# rev_d.net
KiCad netlist of a schematic drawn in EAGLE
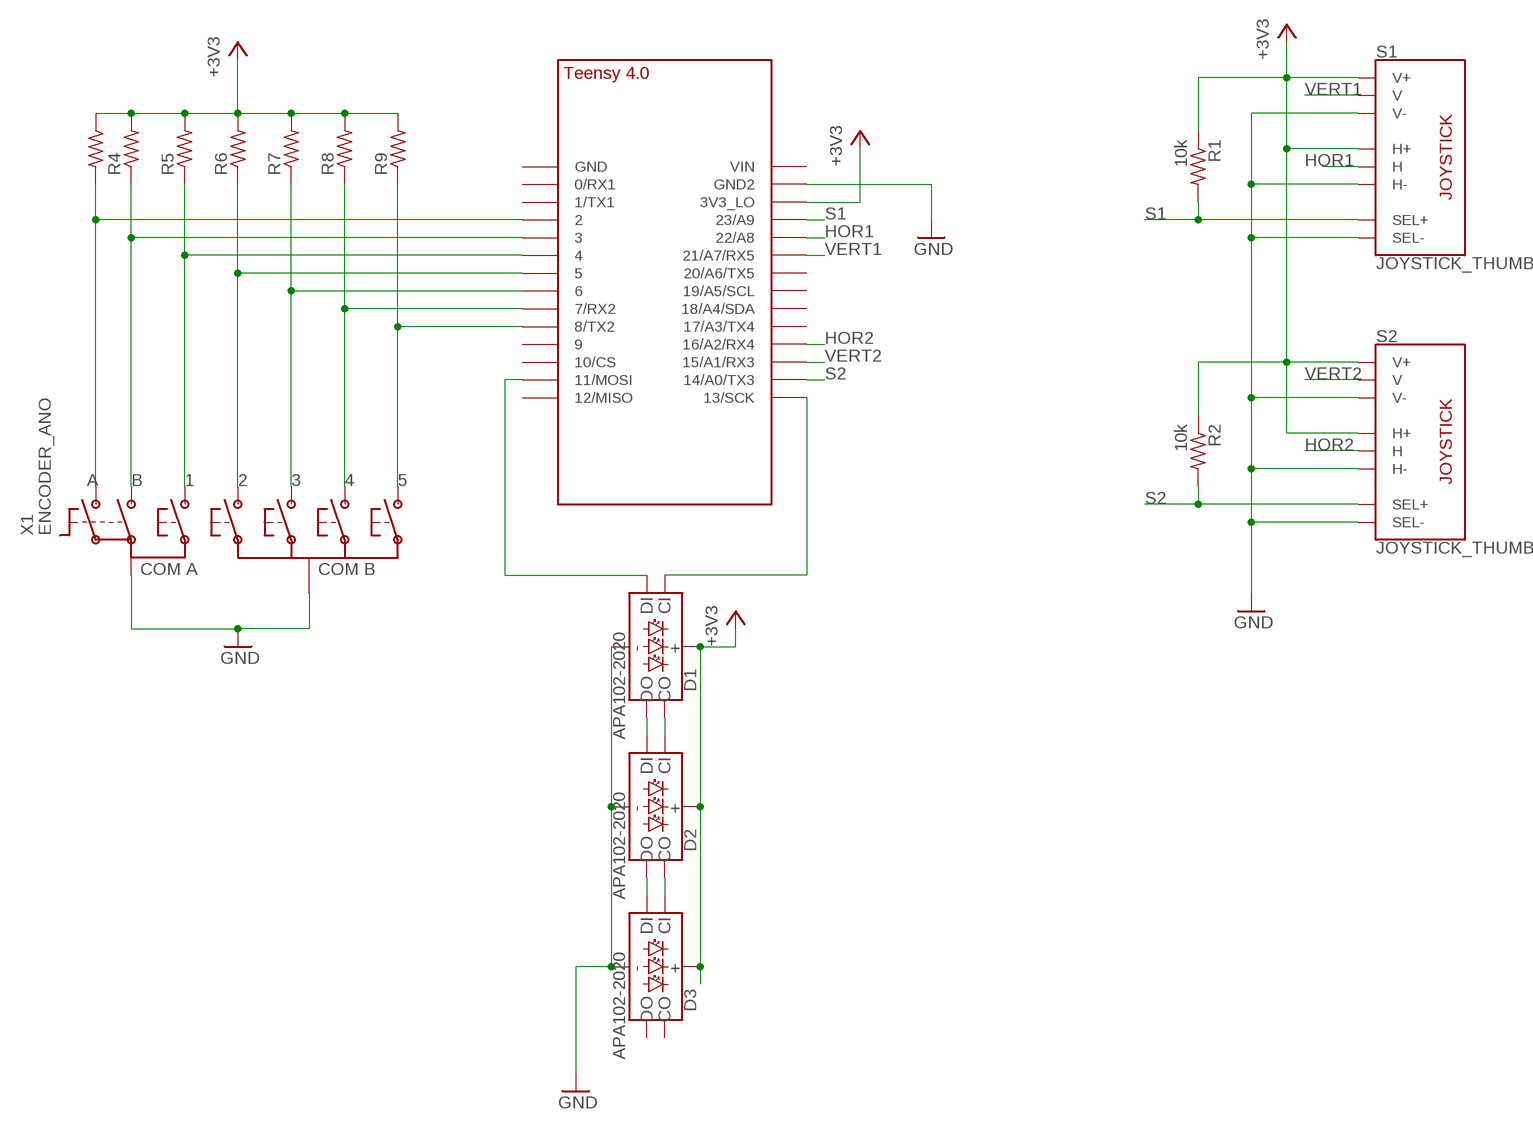
[diagram p0: schematic, sheet 1]

(export (version "E")
  (design (tool "Eeschema 10.0.6"))
  (components
    (comp (ref "D1")
      (value "APA102-2020")
      (footprint "eagle-import:APA102-2020")
      (libsource (lib "eagle-import") (part "APA102-2020"))
    )
    (comp (ref "D2")
      (value "APA102-2020")
      (footprint "eagle-import:APA102-2020")
      (libsource (lib "eagle-import") (part "APA102-2020"))
    )
    (comp (ref "D3")
      (value "APA102-2020")
      (footprint "eagle-import:APA102-2020")
      (libsource (lib "eagle-import") (part "APA102-2020"))
    )
    (comp (ref "MCU")
      (value "TEENSY_4.0-NOBOTTOM")
      (footprint "eagle-import:TEENSY_4.0-NOBOTTOM")
      (libsource (lib "eagle-import") (part "TEENSY_4.0-NOBOTTOM"))
    )
    (comp (ref "R1")
      (value "10k")
      (footprint "eagle-import:R0603")
      (libsource (lib "eagle-import") (part "R-US_R0603"))
    )
    (comp (ref "R2")
      (value "10k")
      (footprint "eagle-import:R0603")
      (libsource (lib "eagle-import") (part "R-US_R0603"))
    )
    (comp (ref "R3")
      (value "10k")
      (footprint "eagle-import:R0603")
      (libsource (lib "eagle-import") (part "R-US_R0603"))
    )
    (comp (ref "R4")
      (value "R-US_R0603")
      (footprint "eagle-import:R0603")
      (libsource (lib "eagle-import") (part "R-US_R0603"))
    )
    (comp (ref "R5")
      (value "R-US_R0603")
      (footprint "eagle-import:R0603")
      (libsource (lib "eagle-import") (part "R-US_R0603"))
    )
    (comp (ref "R6")
      (value "R-US_R0603")
      (footprint "eagle-import:R0603")
      (libsource (lib "eagle-import") (part "R-US_R0603"))
    )
    (comp (ref "R7")
      (value "R-US_R0603")
      (footprint "eagle-import:R0603")
      (libsource (lib "eagle-import") (part "R-US_R0603"))
    )
    (comp (ref "R8")
      (value "R-US_R0603")
      (footprint "eagle-import:R0603")
      (libsource (lib "eagle-import") (part "R-US_R0603"))
    )
    (comp (ref "R9")
      (value "R-US_R0603")
      (footprint "eagle-import:R0603")
      (libsource (lib "eagle-import") (part "R-US_R0603"))
    )
    (comp (ref "S1")
      (value "JOYSTICK_THUMB")
      (footprint "eagle-import:JOYSTICK")
      (libsource (lib "eagle-import") (part "JOYSTICK_THUMB"))
    )
    (comp (ref "S2")
      (value "JOYSTICK_THUMB")
      (footprint "eagle-import:JOYSTICK")
      (libsource (lib "eagle-import") (part "JOYSTICK_THUMB"))
    )
    (comp (ref "X1")
      (value "ENCODER_ANO")
      (footprint "eagle-import:ENCODER_ANO")
      (libsource (lib "eagle-import") (part "ENCODER_ANO"))
    )
  )
  (nets
    (net (code "1") (name "+3V3") (class "Default")
      (node (ref "D1") (pin "VDD") (pinfunction "VCC_VDD") (pintype "bidirectional"))
      (node (ref "D2") (pin "VDD") (pinfunction "VCC_VDD") (pintype "bidirectional"))
      (node (ref "D3") (pin "VDD") (pinfunction "VCC_VDD") (pintype "bidirectional"))
      (node (ref "MCU") (pin "3V3_LO") (pinfunction "3V3_LO_3V3_LO") (pintype "bidirectional"))
      (node (ref "R1") (pin "1") (pinfunction "1_1") (pintype "passive"))
      (node (ref "R2") (pin "1") (pinfunction "1_1") (pintype "passive"))
      (node (ref "R3") (pin "1") (pinfunction "1_1") (pintype "passive"))
      (node (ref "R4") (pin "2") (pinfunction "2_2") (pintype "passive"))
      (node (ref "R5") (pin "2") (pinfunction "2_2") (pintype "passive"))
      (node (ref "R6") (pin "2") (pinfunction "2_2") (pintype "passive"))
      (node (ref "R7") (pin "2") (pinfunction "2_2") (pintype "passive"))
      (node (ref "R8") (pin "2") (pinfunction "2_2") (pintype "passive"))
      (node (ref "R9") (pin "2") (pinfunction "2_2") (pintype "passive"))
      (node (ref "S1") (pin "H1") (pinfunction "H+_H1") (pintype "bidirectional"))
      (node (ref "S1") (pin "V1") (pinfunction "V+_V1") (pintype "bidirectional"))
      (node (ref "S2") (pin "H1") (pinfunction "H+_H1") (pintype "bidirectional"))
      (node (ref "S2") (pin "V1") (pinfunction "V+_V1") (pintype "bidirectional"))
    )
    (net (code "2") (name "/HOR1") (class "Default")
      (node (ref "MCU") (pin "22/A8") (pinfunction "22/A8_22/A8") (pintype "bidirectional"))
      (node (ref "S1") (pin "H2") (pinfunction "H_H2") (pintype "bidirectional"))
    )
    (net (code "3") (name "/HOR2") (class "Default")
      (node (ref "MCU") (pin "16/A2") (pinfunction "16/A2/RX4_16/A2") (pintype "bidirectional"))
      (node (ref "S2") (pin "H2") (pinfunction "H_H2") (pintype "bidirectional"))
    )
    (net (code "4") (name "/S1") (class "Default")
      (node (ref "MCU") (pin "23/A9") (pinfunction "23/A9_23/A9") (pintype "bidirectional"))
      (node (ref "R1") (pin "2") (pinfunction "2_2") (pintype "passive"))
      (node (ref "S1") (pin "B1A") (pinfunction "SEL+_B1A") (pintype "bidirectional"))
    )
    (net (code "5") (name "/S2") (class "Default")
      (node (ref "MCU") (pin "14/A0") (pinfunction "14/A0/TX3_14/A0") (pintype "bidirectional"))
      (node (ref "R2") (pin "2") (pinfunction "2_2") (pintype "passive"))
      (node (ref "S2") (pin "B1A") (pinfunction "SEL+_B1A") (pintype "bidirectional"))
    )
    (net (code "6") (name "/VERT1") (class "Default")
      (node (ref "MCU") (pin "21/A7") (pinfunction "21/A7/RX5_21/A7") (pintype "bidirectional"))
      (node (ref "S1") (pin "V2") (pinfunction "V_V2") (pintype "bidirectional"))
    )
    (net (code "7") (name "/VERT2") (class "Default")
      (node (ref "MCU") (pin "15/A1") (pinfunction "15/A1/RX3_15/A1") (pintype "bidirectional"))
      (node (ref "S2") (pin "V2") (pinfunction "V_V2") (pintype "bidirectional"))
    )
    (net (code "8") (name "GND") (class "Default")
      (node (ref "D1") (pin "GND") (pinfunction "GND_GND") (pintype "bidirectional"))
      (node (ref "D2") (pin "GND") (pinfunction "GND_GND") (pintype "bidirectional"))
      (node (ref "D3") (pin "GND") (pinfunction "GND_GND") (pintype "bidirectional"))
      (node (ref "MCU") (pin "GND2") (pinfunction "GND2_GND2") (pintype "bidirectional"))
      (node (ref "S1") (pin "B2A") (pinfunction "SEL-_B2A") (pintype "bidirectional"))
      (node (ref "S1") (pin "H3") (pinfunction "H-_H3") (pintype "bidirectional"))
      (node (ref "S1") (pin "V3") (pinfunction "V-_V3") (pintype "bidirectional"))
      (node (ref "S2") (pin "B2A") (pinfunction "SEL-_B2A") (pintype "bidirectional"))
      (node (ref "S2") (pin "H3") (pinfunction "H-_H3") (pintype "bidirectional"))
      (node (ref "S2") (pin "V3") (pinfunction "V-_V3") (pintype "bidirectional"))
      (node (ref "X1") (pin "COM_A") (pinfunction "COMA_COM_A") (pintype "passive"))
      (node (ref "X1") (pin "COM_B") (pinfunction "COM_B_COM_B") (pintype "passive"))
    )
    (net (code "9") (name "Net-(D1-CI)") (class "Default")
      (node (ref "D1") (pin "CKI") (pinfunction "CI_CKI") (pintype "bidirectional"))
      (node (ref "MCU") (pin "13/SCK") (pinfunction "13/SCK_13/SCK") (pintype "bidirectional"))
    )
    (net (code "10") (name "Net-(D1-CO)") (class "Default")
      (node (ref "D1") (pin "CKO") (pinfunction "CO_CKO") (pintype "bidirectional"))
      (node (ref "D2") (pin "CKI") (pinfunction "CI_CKI") (pintype "bidirectional"))
    )
    (net (code "11") (name "Net-(D1-DI)") (class "Default")
      (node (ref "D1") (pin "SDI") (pinfunction "DI_SDI") (pintype "bidirectional"))
      (node (ref "MCU") (pin "11/MOSI") (pinfunction "11/MOSI_11/MOSI") (pintype "bidirectional"))
    )
    (net (code "12") (name "Net-(D1-DO)") (class "Default")
      (node (ref "D1") (pin "SDO") (pinfunction "DO_SDO") (pintype "bidirectional"))
      (node (ref "D2") (pin "SDI") (pinfunction "DI_SDI") (pintype "bidirectional"))
    )
    (net (code "13") (name "Net-(D2-CO)") (class "Default")
      (node (ref "D2") (pin "CKO") (pinfunction "CO_CKO") (pintype "bidirectional"))
      (node (ref "D3") (pin "CKI") (pinfunction "CI_CKI") (pintype "bidirectional"))
    )
    (net (code "14") (name "Net-(D2-DO)") (class "Default")
      (node (ref "D2") (pin "SDO") (pinfunction "DO_SDO") (pintype "bidirectional"))
      (node (ref "D3") (pin "SDI") (pinfunction "DI_SDI") (pintype "bidirectional"))
    )
    (net (code "15") (name "Net-(MCU-3)") (class "Default")
      (node (ref "MCU") (pin "3/CANTX") (pinfunction "3_3/CANTX") (pintype "bidirectional"))
      (node (ref "R4") (pin "1") (pinfunction "1_1") (pintype "passive"))
      (node (ref "X1") (pin "B") (pinfunction "B_B") (pintype "passive"))
    )
    (net (code "16") (name "Net-(MCU-4)") (class "Default")
      (node (ref "MCU") (pin "4/CANRX") (pinfunction "4_4/CANRX") (pintype "bidirectional"))
      (node (ref "R5") (pin "1") (pinfunction "1_1") (pintype "passive"))
      (node (ref "X1") (pin "S1") (pinfunction "1_S1") (pintype "passive"))
    )
    (net (code "17") (name "Net-(MCU-7{slash}RX2)") (class "Default")
      (node (ref "MCU") (pin "7") (pinfunction "7/RX2_7") (pintype "bidirectional"))
      (node (ref "R8") (pin "1") (pinfunction "1_1") (pintype "passive"))
      (node (ref "X1") (pin "S4") (pinfunction "S4_S4") (pintype "passive"))
    )
    (net (code "18") (name "Net-(MCU-8{slash}TX2)") (class "Default")
      (node (ref "MCU") (pin "8") (pinfunction "8/TX2_8") (pintype "bidirectional"))
      (node (ref "R9") (pin "1") (pinfunction "1_1") (pintype "passive"))
      (node (ref "X1") (pin "S5") (pinfunction "S5_S5") (pintype "passive"))
    )
    (net (code "19") (name "Net-(MCU-Pad2)") (class "Default")
      (node (ref "MCU") (pin "2") (pinfunction "2_2") (pintype "bidirectional"))
      (node (ref "R3") (pin "2") (pinfunction "2_2") (pintype "passive"))
      (node (ref "X1") (pin "A") (pinfunction "A_A") (pintype "passive"))
    )
    (net (code "20") (name "Net-(MCU-Pad5)") (class "Default")
      (node (ref "MCU") (pin "5") (pinfunction "5_5") (pintype "bidirectional"))
      (node (ref "R6") (pin "1") (pinfunction "1_1") (pintype "passive"))
      (node (ref "X1") (pin "S2") (pinfunction "S2_S2") (pintype "passive"))
    )
    (net (code "21") (name "Net-(MCU-Pad6)") (class "Default")
      (node (ref "MCU") (pin "6") (pinfunction "6_6") (pintype "bidirectional"))
      (node (ref "R7") (pin "1") (pinfunction "1_1") (pintype "passive"))
      (node (ref "X1") (pin "S3") (pinfunction "S3_S3") (pintype "passive"))
    )
    (net (code "22") (name "unconnected-(D3-CO-PadCKO)") (class "Default")
      (node (ref "D3") (pin "CKO") (pinfunction "CO_CKO") (pintype "bidirectional"))
    )
    (net (code "23") (name "unconnected-(D3-DO-PadSDO)") (class "Default")
      (node (ref "D3") (pin "SDO") (pinfunction "DO_SDO") (pintype "bidirectional"))
    )
    (net (code "24") (name "unconnected-(MCU-0{slash}RX1-Pad0{slash}RX)") (class "Default")
      (node (ref "MCU") (pin "0/RX") (pinfunction "0/RX1_0/RX") (pintype "bidirectional"))
    )
    (net (code "25") (name "unconnected-(MCU-1{slash}TX1-Pad1{slash}TX)") (class "Default")
      (node (ref "MCU") (pin "1/TX") (pinfunction "1/TX1_1/TX") (pintype "bidirectional"))
    )
    (net (code "26") (name "unconnected-(MCU-9-Pad9{slash}CS)") (class "Default")
      (node (ref "MCU") (pin "9/CS") (pinfunction "9_9/CS") (pintype "bidirectional"))
    )
    (net (code "27") (name "unconnected-(MCU-17{slash}A3{slash}TX4-Pad17{slash}A3)") (class "Default")
      (node (ref "MCU") (pin "17/A3") (pinfunction "17/A3/TX4_17/A3") (pintype "bidirectional"))
    )
    (net (code "28") (name "unconnected-(MCU-20{slash}A6{slash}TX5-Pad20{slash}A6)") (class "Default")
      (node (ref "MCU") (pin "20/A6") (pinfunction "20/A6/TX5_20/A6") (pintype "bidirectional"))
    )
    (net (code "29") (name "unconnected-(MCU-Pad10{slash}CS)") (class "Default")
      (node (ref "MCU") (pin "10/CS") (pinfunction "10/CS_10/CS") (pintype "bidirectional"))
    )
    (net (code "30") (name "unconnected-(MCU-Pad12{slash}MISO)") (class "Default")
      (node (ref "MCU") (pin "12/MISO") (pinfunction "12/MISO_12/MISO") (pintype "bidirectional"))
    )
    (net (code "31") (name "unconnected-(MCU-Pad18{slash}A4{slash}SDA)") (class "Default")
      (node (ref "MCU") (pin "18/A4/SDA") (pinfunction "18/A4/SDA_18/A4/SDA") (pintype "bidirectional"))
    )
    (net (code "32") (name "unconnected-(MCU-Pad19{slash}A5{slash}SCL)") (class "Default")
      (node (ref "MCU") (pin "19/A5/SCL") (pinfunction "19/A5/SCL_19/A5/SCL") (pintype "bidirectional"))
    )
    (net (code "33") (name "unconnected-(MCU-PadGND)") (class "Default")
      (node (ref "MCU") (pin "GND") (pinfunction "GND_GND") (pintype "bidirectional"))
    )
    (net (code "34") (name "unconnected-(MCU-PadVIN)") (class "Default")
      (node (ref "MCU") (pin "VIN") (pinfunction "VIN_VIN") (pintype "bidirectional"))
    )
  )
)
